# led-candle.net
KiCad netlist of a schematic drawn in EAGLE
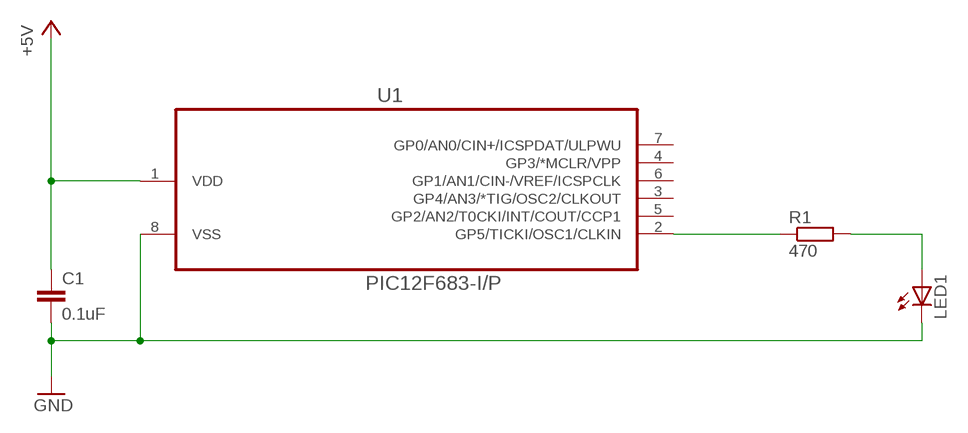
[diagram p0: schematic, sheet 1]

(export (version "E")
  (design (tool "Eeschema 10.0.6"))
  (components
    (comp (ref "C1")
      (value "0.1uF")
      (footprint "eagle-import:C2.5-3")
      (libsource (lib "eagle-import") (part "C2,5-3"))
    )
    (comp (ref "LED1")
      (value "LED")
      (footprint "eagle-import:SMARTLED-TTW")
      (libsource (lib "eagle-import") (part "LED"))
    )
    (comp (ref "R1")
      (value "470")
      (footprint "eagle-import:0204V")
      (libsource (lib "eagle-import") (part "R-EU_0204/2V"))
    )
    (comp (ref "U1")
      (value "PIC12F683-I/P")
      (footprint "eagle-import:DIP254P762X533-8")
      (libsource (lib "eagle-import") (part "PIC12F683-I/P"))
    )
  )
  (nets
    (net (code "1") (name "+5V") (class "Default")
      (node (ref "C1") (pin "1") (pinfunction "1_1") (pintype "passive"))
      (node (ref "U1") (pin "1") (pinfunction "VDD_1") (pintype "power_in"))
    )
    (net (code "2") (name "GND") (class "Default")
      (node (ref "C1") (pin "2") (pinfunction "2_2") (pintype "passive"))
      (node (ref "LED1") (pin "C@1") (pinfunction "C_C@1") (pintype "passive"))
      (node (ref "U1") (pin "8") (pinfunction "VSS_8") (pintype "passive"))
    )
    (net (code "3") (name "Net-(LED1-A)") (class "Default")
      (node (ref "LED1") (pin "A@1") (pinfunction "A_A@1") (pintype "passive"))
      (node (ref "R1") (pin "2") (pinfunction "2_2") (pintype "passive"))
    )
    (net (code "4") (name "Net-(U1-GP5{slash}TICKI{slash}OSC1{slash}CLKIN)") (class "Default")
      (node (ref "R1") (pin "1") (pinfunction "1_1") (pintype "passive"))
      (node (ref "U1") (pin "2") (pinfunction "GP5/TICKI/OSC1/CLKIN_2") (pintype "bidirectional"))
    )
    (net (code "5") (name "unconnected-(U1-GP0{slash}AN0{slash}CIN+{slash}ICSPDAT{slash}ULPWU-Pad7)") (class "Default")
      (node (ref "U1") (pin "7") (pinfunction "GP0/AN0/CIN+/ICSPDAT/ULPWU_7") (pintype "bidirectional"))
    )
    (net (code "6") (name "unconnected-(U1-GP1{slash}AN1{slash}CIN-{slash}VREF{slash}ICSPCLK-Pad6)") (class "Default")
      (node (ref "U1") (pin "6") (pinfunction "GP1/AN1/CIN-/VREF/ICSPCLK_6") (pintype "bidirectional"))
    )
    (net (code "7") (name "unconnected-(U1-GP2{slash}AN2{slash}T0CKI{slash}INT{slash}COUT{slash}CCP1-Pad5)") (class "Default")
      (node (ref "U1") (pin "5") (pinfunction "GP2/AN2/T0CKI/INT/COUT/CCP1_5") (pintype "bidirectional"))
    )
    (net (code "8") (name "unconnected-(U1-GP3{slash}*MCLR{slash}VPP-Pad4)") (class "Default")
      (node (ref "U1") (pin "4") (pinfunction "GP3/*MCLR/VPP_4") (pintype "bidirectional"))
    )
    (net (code "9") (name "unconnected-(U1-GP4{slash}AN3{slash}*TIG{slash}OSC2{slash}CLKOUT-Pad3)") (class "Default")
      (node (ref "U1") (pin "3") (pinfunction "GP4/AN3/*TIG/OSC2/CLKOUT_3") (pintype "bidirectional"))
    )
  )
)
